# Cell_Module_v1.net
KiCad netlist of a schematic drawn in EAGLE
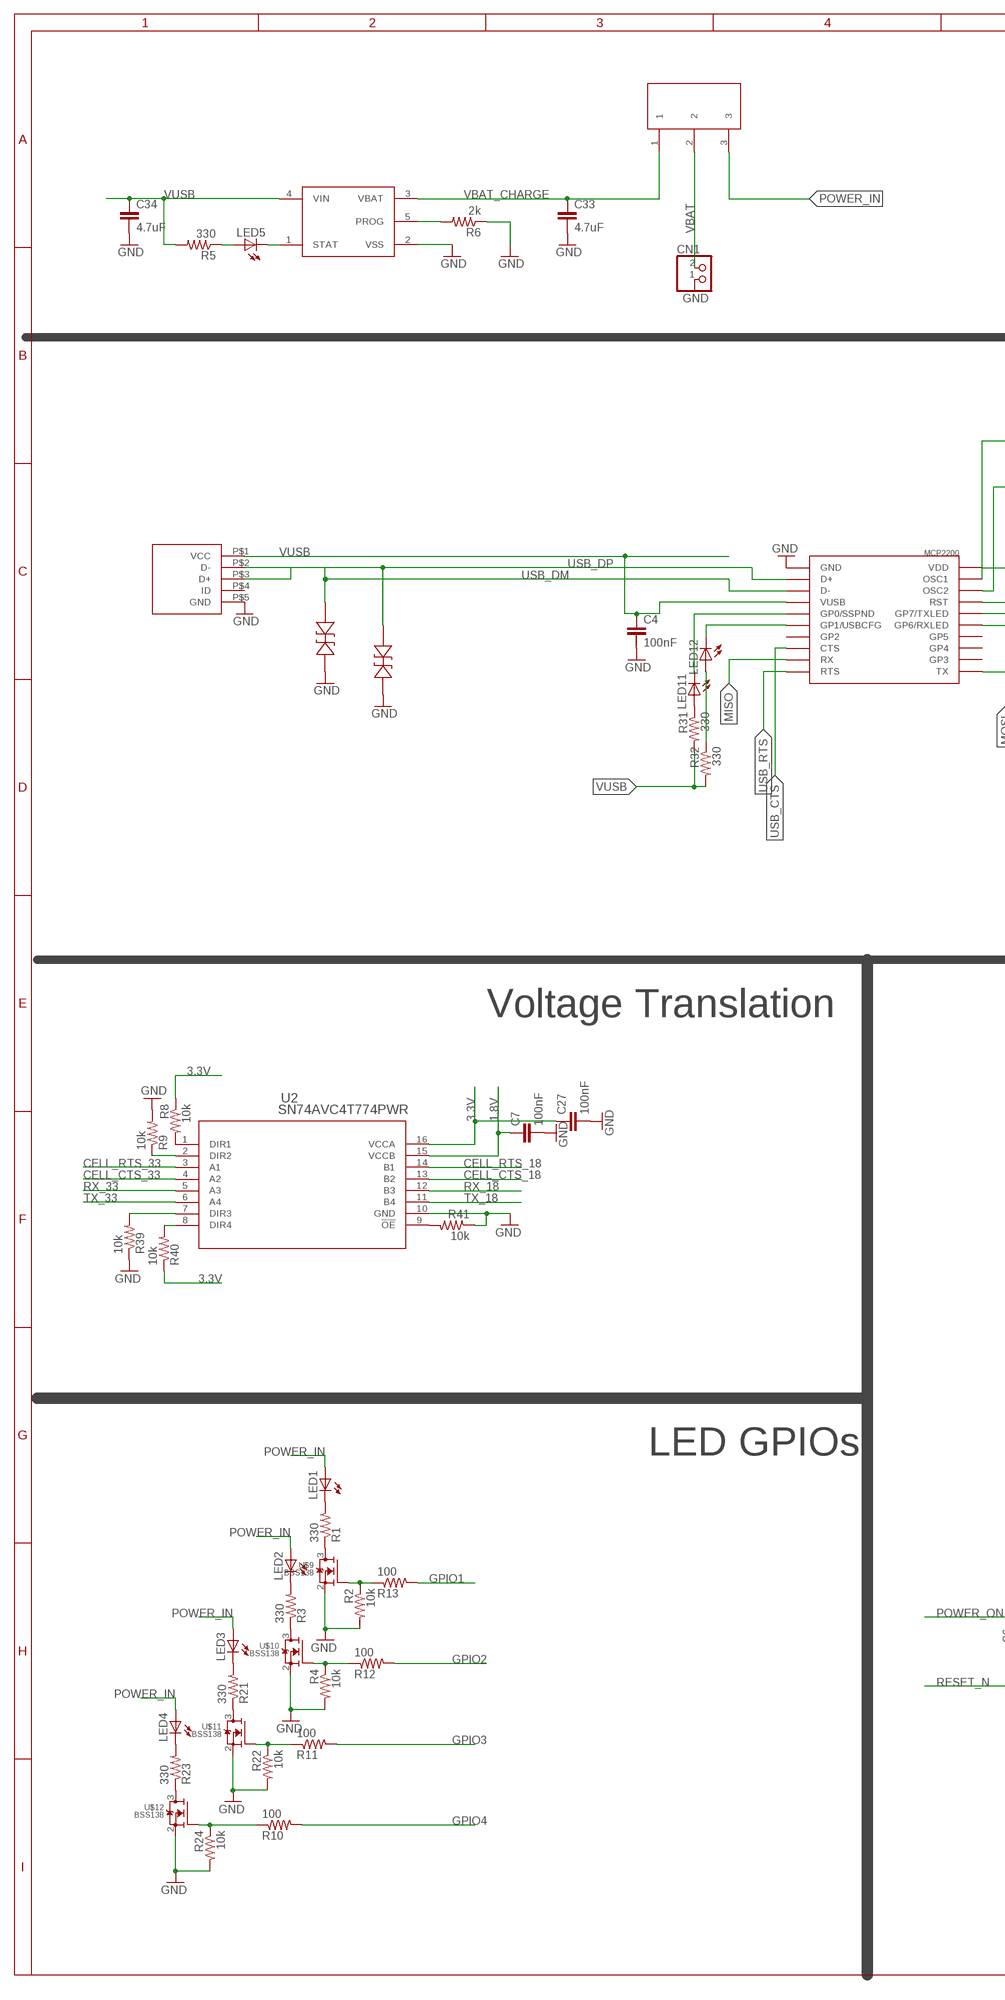
[diagram p0: schematic, sheet 1, part 1 of 2]
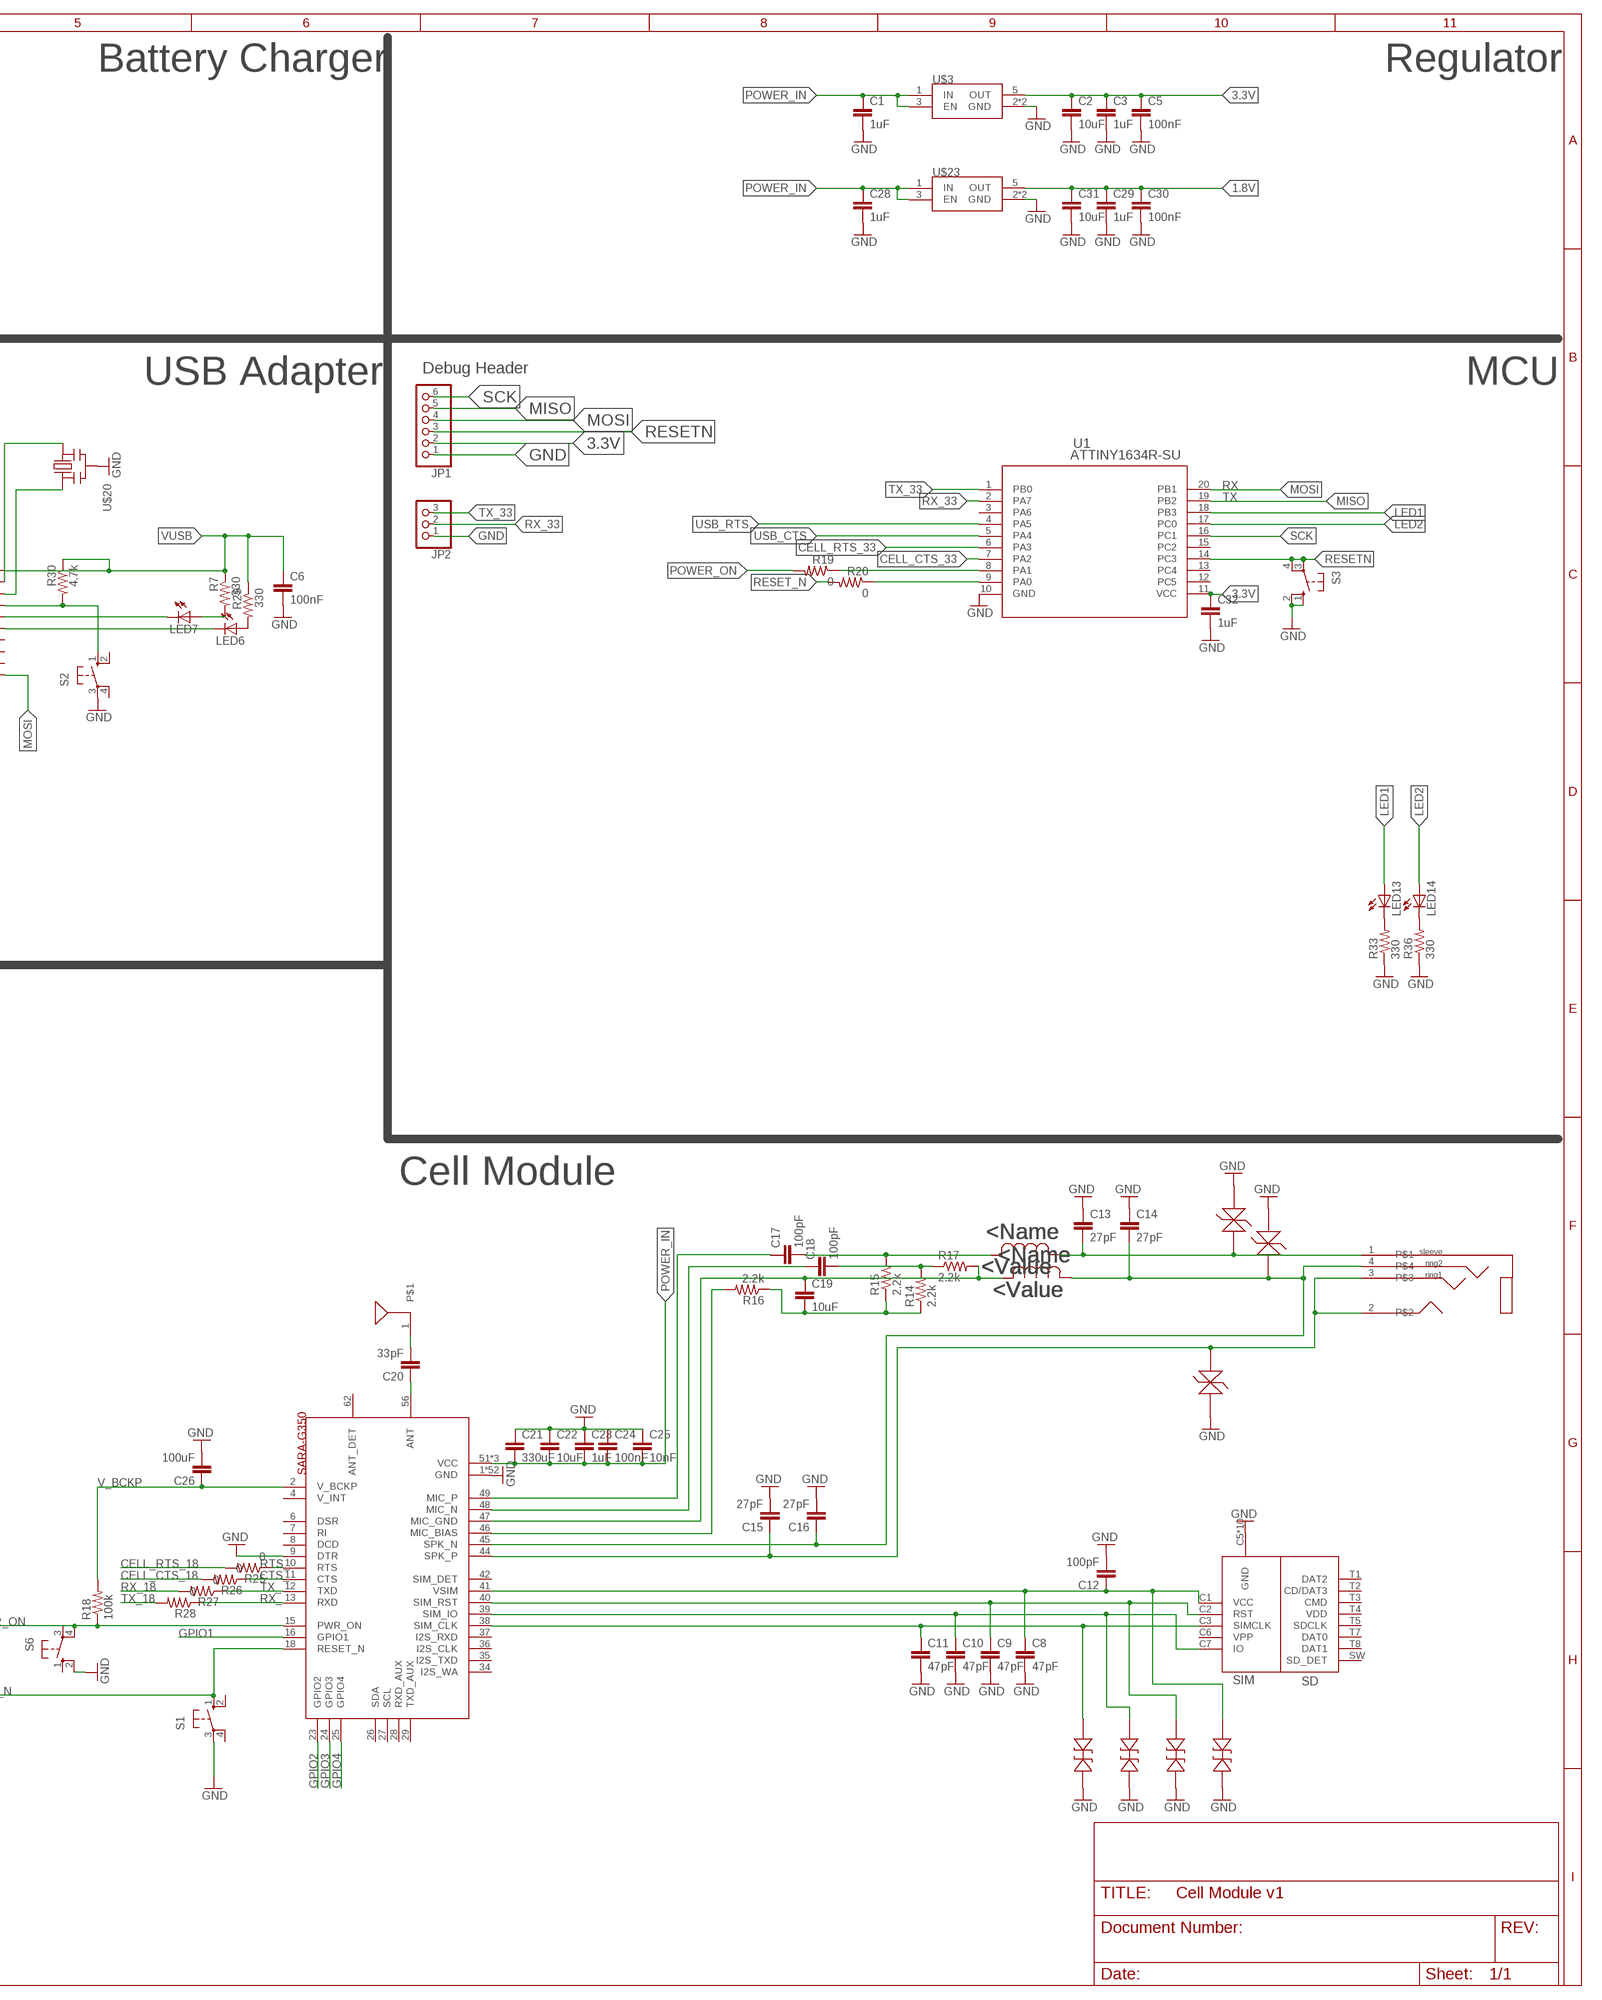
[diagram p1: schematic, sheet 1, part 2 of 2]

(export (version "E")
  (design (tool "Eeschema 10.0.6"))
  (components
    (comp (ref "C1")
      (value "1uF")
      (footprint "eagle-import:C0402")
      (libsource (lib "eagle-import") (part "C-EUC0402"))
    )
    (comp (ref "C2")
      (value "10uF")
      (footprint "eagle-import:C0603")
      (libsource (lib "eagle-import") (part "C-EUC0603"))
    )
    (comp (ref "C3")
      (value "1uF")
      (footprint "eagle-import:C0402")
      (libsource (lib "eagle-import") (part "C-EUC0402"))
    )
    (comp (ref "C4")
      (value "100nF")
      (footprint "eagle-import:C0402")
      (libsource (lib "eagle-import") (part "C-EUC0402"))
    )
    (comp (ref "C5")
      (value "100nF")
      (footprint "eagle-import:C0402")
      (libsource (lib "eagle-import") (part "C-EUC0402"))
    )
    (comp (ref "C6")
      (value "100nF")
      (footprint "eagle-import:C0402")
      (libsource (lib "eagle-import") (part "C-EUC0402"))
    )
    (comp (ref "C7")
      (value "100nF")
      (footprint "eagle-import:C0402")
      (libsource (lib "eagle-import") (part "C-EUC0402"))
    )
    (comp (ref "C8")
      (value "47pF")
      (footprint "eagle-import:C0402")
      (libsource (lib "eagle-import") (part "C-EUC0402"))
    )
    (comp (ref "C9")
      (value "47pF")
      (footprint "eagle-import:C0402")
      (libsource (lib "eagle-import") (part "C-EUC0402"))
    )
    (comp (ref "C10")
      (value "47pF")
      (footprint "eagle-import:C0402")
      (libsource (lib "eagle-import") (part "C-EUC0402"))
    )
    (comp (ref "C11")
      (value "47pF")
      (footprint "eagle-import:C0402")
      (libsource (lib "eagle-import") (part "C-EUC0402"))
    )
    (comp (ref "C12")
      (value "100pF")
      (footprint "eagle-import:C0402")
      (libsource (lib "eagle-import") (part "C-EUC0402"))
    )
    (comp (ref "C13")
      (value "27pF")
      (footprint "eagle-import:C0402")
      (libsource (lib "eagle-import") (part "C-EUC0402"))
    )
    (comp (ref "C14")
      (value "27pF")
      (footprint "eagle-import:C0402")
      (libsource (lib "eagle-import") (part "C-EUC0402"))
    )
    (comp (ref "C15")
      (value "27pF")
      (footprint "eagle-import:C0402")
      (libsource (lib "eagle-import") (part "C-EUC0402"))
    )
    (comp (ref "C16")
      (value "27pF")
      (footprint "eagle-import:C0402")
      (libsource (lib "eagle-import") (part "C-EUC0402"))
    )
    (comp (ref "C17")
      (value "100pF")
      (footprint "eagle-import:C0402")
      (libsource (lib "eagle-import") (part "C-EUC0402"))
    )
    (comp (ref "C18")
      (value "100pF")
      (footprint "eagle-import:C0402")
      (libsource (lib "eagle-import") (part "C-EUC0402"))
    )
    (comp (ref "C19")
      (value "10uF")
      (footprint "eagle-import:C0603")
      (libsource (lib "eagle-import") (part "C-EUC0603"))
    )
    (comp (ref "C20")
      (value "33pF")
      (footprint "eagle-import:C0402")
      (libsource (lib "eagle-import") (part "C-EUC0402"))
    )
    (comp (ref "C21")
      (value "330uF")
      (footprint "eagle-import:C1210")
      (libsource (lib "eagle-import") (part "C-EUC1210"))
    )
    (comp (ref "C22")
      (value "10uF")
      (footprint "eagle-import:C0603")
      (libsource (lib "eagle-import") (part "C-EUC0603"))
    )
    (comp (ref "C23")
      (value "1uF")
      (footprint "eagle-import:C0402")
      (libsource (lib "eagle-import") (part "C-EUC0402"))
    )
    (comp (ref "C24")
      (value "100nF")
      (footprint "eagle-import:C0402")
      (libsource (lib "eagle-import") (part "C-EUC0402"))
    )
    (comp (ref "C25")
      (value "10nF")
      (footprint "eagle-import:C0402")
      (libsource (lib "eagle-import") (part "C-EUC0402"))
    )
    (comp (ref "C26")
      (value "100uF")
      (footprint "eagle-import:C1206")
      (libsource (lib "eagle-import") (part "C-EUC1206"))
    )
    (comp (ref "C27")
      (value "100nF")
      (footprint "eagle-import:C0402")
      (libsource (lib "eagle-import") (part "C-EUC0402"))
    )
    (comp (ref "C28")
      (value "1uF")
      (footprint "eagle-import:C0402")
      (libsource (lib "eagle-import") (part "C-EUC0402"))
    )
    (comp (ref "C29")
      (value "1uF")
      (footprint "eagle-import:C0402")
      (libsource (lib "eagle-import") (part "C-EUC0402"))
    )
    (comp (ref "C30")
      (value "100nF")
      (footprint "eagle-import:C0402")
      (libsource (lib "eagle-import") (part "C-EUC0402"))
    )
    (comp (ref "C31")
      (value "10uF")
      (footprint "eagle-import:C0603")
      (libsource (lib "eagle-import") (part "C-EUC0603"))
    )
    (comp (ref "C32")
      (value "1uF")
      (footprint "eagle-import:C0402")
      (libsource (lib "eagle-import") (part "C-EUC0402"))
    )
    (comp (ref "C33")
      (value "4.7uF")
      (footprint "eagle-import:C0402")
      (libsource (lib "eagle-import") (part "C-EUC0402"))
    )
    (comp (ref "C34")
      (value "4.7uF")
      (footprint "eagle-import:C0402")
      (libsource (lib "eagle-import") (part "C-EUC0402"))
    )
    (comp (ref "CN1")
      (value "JST_2PIN-THM")
      (footprint "eagle-import:JST-PH-2-THM")
      (libsource (lib "eagle-import") (part "JST_2PIN-THM"))
    )
    (comp (ref "CR1")
      (value "PESD0402-140")
      (footprint "eagle-import:PESD0402")
      (fields (field (name "MANUFACTURER_PART_NUMBER") "PESD0402140"))
      (libsource (lib "eagle-import") (part "PESD0402-140"))
    )
    (comp (ref "CR2")
      (value "PESD0402-140")
      (footprint "eagle-import:PESD0402")
      (fields (field (name "MANUFACTURER_PART_NUMBER") "PESD0402140"))
      (libsource (lib "eagle-import") (part "PESD0402-140"))
    )
    (comp (ref "CR3")
      (value "PESD0402-140")
      (footprint "eagle-import:PESD0402")
      (fields (field (name "MANUFACTURER_PART_NUMBER") "PESD0402140"))
      (libsource (lib "eagle-import") (part "PESD0402-140"))
    )
    (comp (ref "CR4")
      (value "PESD0402-140")
      (footprint "eagle-import:PESD0402")
      (fields (field (name "MANUFACTURER_PART_NUMBER") "PESD0402140"))
      (libsource (lib "eagle-import") (part "PESD0402-140"))
    )
    (comp (ref "CR5")
      (value "PESD0402-140")
      (footprint "eagle-import:PESD0402")
      (fields (field (name "MANUFACTURER_PART_NUMBER") "PESD0402140"))
      (libsource (lib "eagle-import") (part "PESD0402-140"))
    )
    (comp (ref "CR6")
      (value "PESD0402-140")
      (footprint "eagle-import:PESD0402")
      (fields (field (name "MANUFACTURER_PART_NUMBER") "PESD0402140"))
      (libsource (lib "eagle-import") (part "PESD0402-140"))
    )
    (comp (ref "JP1")
      (value "PINHD-1X6")
      (footprint "eagle-import:1X06")
      (libsource (lib "eagle-import") (part "PINHD-1X6"))
    )
    (comp (ref "JP2")
      (value "PINHD-1X3")
      (footprint "eagle-import:1X03")
      (libsource (lib "eagle-import") (part "PINHD-1X3"))
    )
    (comp (ref "LED1")
      (value "LEDCHIP-LED0805")
      (footprint "eagle-import:CHIP-LED0805")
      (libsource (lib "eagle-import") (part "LEDCHIP-LED0805"))
    )
    (comp (ref "LED2")
      (value "LEDCHIP-LED0805")
      (footprint "eagle-import:CHIP-LED0805")
      (libsource (lib "eagle-import") (part "LEDCHIP-LED0805"))
    )
    (comp (ref "LED3")
      (value "LEDCHIP-LED0805")
      (footprint "eagle-import:CHIP-LED0805")
      (libsource (lib "eagle-import") (part "LEDCHIP-LED0805"))
    )
    (comp (ref "LED4")
      (value "LEDCHIP-LED0805")
      (footprint "eagle-import:CHIP-LED0805")
      (libsource (lib "eagle-import") (part "LEDCHIP-LED0805"))
    )
    (comp (ref "LED5")
      (value "LEDCHIP-LED0603")
      (footprint "eagle-import:CHIP-LED0603")
      (libsource (lib "eagle-import") (part "LEDCHIP-LED0603"))
    )
    (comp (ref "LED6")
      (value "LEDCHIP-LED0805")
      (footprint "eagle-import:CHIP-LED0805")
      (libsource (lib "eagle-import") (part "LEDCHIP-LED0805"))
    )
    (comp (ref "LED7")
      (value "LEDCHIP-LED0805")
      (footprint "eagle-import:CHIP-LED0805")
      (libsource (lib "eagle-import") (part "LEDCHIP-LED0805"))
    )
    (comp (ref "LED11")
      (value "LEDCHIP-LED0805")
      (footprint "eagle-import:CHIP-LED0805")
      (libsource (lib "eagle-import") (part "LEDCHIP-LED0805"))
    )
    (comp (ref "LED12")
      (value "LEDCHIP-LED0805")
      (footprint "eagle-import:CHIP-LED0805")
      (libsource (lib "eagle-import") (part "LEDCHIP-LED0805"))
    )
    (comp (ref "LED13")
      (value "LEDCHIP-LED0805")
      (footprint "eagle-import:CHIP-LED0805")
      (libsource (lib "eagle-import") (part "LEDCHIP-LED0805"))
    )
    (comp (ref "LED14")
      (value "LEDCHIP-LED0805")
      (footprint "eagle-import:CHIP-LED0805")
      (libsource (lib "eagle-import") (part "LEDCHIP-LED0805"))
    )
    (comp (ref "R1")
      (value "330")
      (footprint "eagle-import:R0402")
      (libsource (lib "eagle-import") (part "R-US_R0402"))
    )
    (comp (ref "R2")
      (value "10k")
      (footprint "eagle-import:R0402")
      (libsource (lib "eagle-import") (part "R-US_R0402"))
    )
    (comp (ref "R3")
      (value "330")
      (footprint "eagle-import:R0402")
      (libsource (lib "eagle-import") (part "R-US_R0402"))
    )
    (comp (ref "R4")
      (value "10k")
      (footprint "eagle-import:R0402")
      (libsource (lib "eagle-import") (part "R-US_R0402"))
    )
    (comp (ref "R5")
      (value "330")
      (footprint "eagle-import:R0402")
      (libsource (lib "eagle-import") (part "R-US_R0402"))
    )
    (comp (ref "R6")
      (value "2k")
      (footprint "eagle-import:R0402")
      (libsource (lib "eagle-import") (part "R-US_R0402"))
    )
    (comp (ref "R7")
      (value "330")
      (footprint "eagle-import:R0402")
      (libsource (lib "eagle-import") (part "R-US_R0402"))
    )
    (comp (ref "R8")
      (value "10k")
      (footprint "eagle-import:R0402")
      (libsource (lib "eagle-import") (part "R-US_R0402"))
    )
    (comp (ref "R9")
      (value "10k")
      (footprint "eagle-import:R0402")
      (libsource (lib "eagle-import") (part "R-US_R0402"))
    )
    (comp (ref "R10")
      (value "100")
      (footprint "eagle-import:R0402")
      (libsource (lib "eagle-import") (part "R-US_R0402"))
    )
    (comp (ref "R11")
      (value "100")
      (footprint "eagle-import:R0402")
      (libsource (lib "eagle-import") (part "R-US_R0402"))
    )
    (comp (ref "R12")
      (value "100")
      (footprint "eagle-import:R0402")
      (libsource (lib "eagle-import") (part "R-US_R0402"))
    )
    (comp (ref "R13")
      (value "100")
      (footprint "eagle-import:R0402")
      (libsource (lib "eagle-import") (part "R-US_R0402"))
    )
    (comp (ref "R14")
      (value "2.2k")
      (footprint "eagle-import:R0402")
      (libsource (lib "eagle-import") (part "R-US_R0402"))
    )
    (comp (ref "R15")
      (value "2.2k")
      (footprint "eagle-import:R0402")
      (libsource (lib "eagle-import") (part "R-US_R0402"))
    )
    (comp (ref "R16")
      (value "2.2k")
      (footprint "eagle-import:R0402")
      (libsource (lib "eagle-import") (part "R-US_R0402"))
    )
    (comp (ref "R17")
      (value "2.2k")
      (footprint "eagle-import:R0402")
      (libsource (lib "eagle-import") (part "R-US_R0402"))
    )
    (comp (ref "R18")
      (value "100k")
      (footprint "eagle-import:R0402")
      (libsource (lib "eagle-import") (part "R-US_R0402"))
    )
    (comp (ref "R19")
      (value "0")
      (footprint "eagle-import:R0402")
      (libsource (lib "eagle-import") (part "R-US_R0402"))
    )
    (comp (ref "R20")
      (value "0")
      (footprint "eagle-import:R0402")
      (libsource (lib "eagle-import") (part "R-US_R0402"))
    )
    (comp (ref "R21")
      (value "330")
      (footprint "eagle-import:R0402")
      (libsource (lib "eagle-import") (part "R-US_R0402"))
    )
    (comp (ref "R22")
      (value "10k")
      (footprint "eagle-import:R0402")
      (libsource (lib "eagle-import") (part "R-US_R0402"))
    )
    (comp (ref "R23")
      (value "330")
      (footprint "eagle-import:R0402")
      (libsource (lib "eagle-import") (part "R-US_R0402"))
    )
    (comp (ref "R24")
      (value "10k")
      (footprint "eagle-import:R0402")
      (libsource (lib "eagle-import") (part "R-US_R0402"))
    )
    (comp (ref "R25")
      (value "0")
      (footprint "eagle-import:R0402")
      (libsource (lib "eagle-import") (part "R-US_R0402"))
    )
    (comp (ref "R26")
      (value "0")
      (footprint "eagle-import:R0402")
      (libsource (lib "eagle-import") (part "R-US_R0402"))
    )
    (comp (ref "R27")
      (value "0")
      (footprint "eagle-import:R0402")
      (libsource (lib "eagle-import") (part "R-US_R0402"))
    )
    (comp (ref "R28")
      (value "0")
      (footprint "eagle-import:R0402")
      (libsource (lib "eagle-import") (part "R-US_R0402"))
    )
    (comp (ref "R29")
      (value "330")
      (footprint "eagle-import:R0402")
      (libsource (lib "eagle-import") (part "R-US_R0402"))
    )
    (comp (ref "R30")
      (value "4.7k")
      (footprint "eagle-import:R0402")
      (libsource (lib "eagle-import") (part "R-US_R0402"))
    )
    (comp (ref "R31")
      (value "330")
      (footprint "eagle-import:R0402")
      (libsource (lib "eagle-import") (part "R-US_R0402"))
    )
    (comp (ref "R32")
      (value "330")
      (footprint "eagle-import:R0402")
      (libsource (lib "eagle-import") (part "R-US_R0402"))
    )
    (comp (ref "R33")
      (value "330")
      (footprint "eagle-import:R0402")
      (libsource (lib "eagle-import") (part "R-US_R0402"))
    )
    (comp (ref "R36")
      (value "330")
      (footprint "eagle-import:R0402")
      (libsource (lib "eagle-import") (part "R-US_R0402"))
    )
    (comp (ref "R39")
      (value "10k")
      (footprint "eagle-import:R0402")
      (libsource (lib "eagle-import") (part "R-US_R0402"))
    )
    (comp (ref "R40")
      (value "10k")
      (footprint "eagle-import:R0402")
      (libsource (lib "eagle-import") (part "R-US_R0402"))
    )
    (comp (ref "R41")
      (value "10k")
      (footprint "eagle-import:R0402")
      (libsource (lib "eagle-import") (part "R-US_R0402"))
    )
    (comp (ref "S1")
      (value "10-XX")
      (footprint "eagle-import:B3F-10XX")
      (fields (field (name "MPN") "B3F-1000"))
      (libsource (lib "eagle-import") (part "10-XX"))
    )
    (comp (ref "S2")
      (value "10-XX")
      (footprint "eagle-import:B3F-10XX")
      (fields (field (name "MPN") "B3F-1000"))
      (libsource (lib "eagle-import") (part "10-XX"))
    )
    (comp (ref "S3")
      (value "10-XX")
      (footprint "eagle-import:B3F-10XX")
      (fields (field (name "MPN") "B3F-1000"))
      (libsource (lib "eagle-import") (part "10-XX"))
    )
    (comp (ref "S6")
      (value "10-XX")
      (footprint "eagle-import:B3F-10XX")
      (fields (field (name "MPN") "B3F-1000"))
      (libsource (lib "eagle-import") (part "10-XX"))
    )
    (comp (ref "U$1")
      (value "SARA-G350")
      (footprint "eagle-import:SARA-G350")
      (libsource (lib "eagle-import") (part "SARA-G350"))
    )
    (comp (ref "U$2")
      (value "SIM_SD_MOLEX")
      (footprint "eagle-import:SIM_SD_MOLEX")
      (libsource (lib "eagle-import") (part "SIM_SD_MOLEX"))
    )
    (comp (ref "U$3")
      (value "TPS782XX")
      (footprint "eagle-import:SOT23-5L")
      (libsource (lib "eagle-import") (part "TPS782XX"))
    )
    (comp (ref "U$4")
      (value "MCP73831")
      (footprint "eagle-import:SOT23-5L")
      (libsource (lib "eagle-import") (part "MCP73831"))
    )
    (comp (ref "U$5")
      (value "MICRO_USB")
      (footprint "eagle-import:MOLEX_USB")
      (libsource (lib "eagle-import") (part "MICRO_USB"))
    )
    (comp (ref "U$6")
      (value "SPDT_THRU")
      (footprint "eagle-import:SPDT_THRU")
      (libsource (lib "eagle-import") (part "SPDT_THRU"))
    )
    (comp (ref "U$7")
      (value "A10340")
      (footprint "eagle-import:A10340")
      (libsource (lib "eagle-import") (part "A10340"))
    )
    (comp (ref "U$8")
      (value "SJ-43514-SMT-TR")
      (footprint "eagle-import:SJ-43514-SMT-TR")
      (libsource (lib "eagle-import") (part "SJ-43514-SMT-TR"))
    )
    (comp (ref "U$9")
      (value "BSS138")
      (footprint "eagle-import:SOT23-3")
      (libsource (lib "eagle-import") (part "BSS138"))
    )
    (comp (ref "U$10")
      (value "BSS138")
      (footprint "eagle-import:SOT23-3")
      (libsource (lib "eagle-import") (part "BSS138"))
    )
    (comp (ref "U$11")
      (value "BSS138")
      (footprint "eagle-import:SOT23-3")
      (libsource (lib "eagle-import") (part "BSS138"))
    )
    (comp (ref "U$12")
      (value "BSS138")
      (footprint "eagle-import:SOT23-3")
      (libsource (lib "eagle-import") (part "BSS138"))
    )
    (comp (ref "U$13")
      (value "LQG15HS82NJ02")
      (footprint "eagle-import:0402")
      (libsource (lib "eagle-import") (part "LQG15HS82NJ02"))
    )
    (comp (ref "U$14")
      (value "LQG15HS82NJ02")
      (footprint "eagle-import:0402")
      (libsource (lib "eagle-import") (part "LQG15HS82NJ02"))
    )
    (comp (ref "U$16")
      (value "CG0402MLE-18G")
      (footprint "eagle-import:0402")
      (libsource (lib "eagle-import") (part "CG0402MLE-18G"))
    )
    (comp (ref "U$17")
      (value "CG0402MLE-18G")
      (footprint "eagle-import:0402")
      (libsource (lib "eagle-import") (part "CG0402MLE-18G"))
    )
    (comp (ref "U$18")
      (value "CG0402MLE-18G")
      (footprint "eagle-import:0402")
      (libsource (lib "eagle-import") (part "CG0402MLE-18G"))
    )
    (comp (ref "U$19")
      (value "MCP2200")
      (footprint "eagle-import:SOIC20_65PITCH_LARGER")
      (libsource (lib "eagle-import") (part "MCP2200"))
    )
    (comp (ref "U$20")
      (value "CERMOSCILL-AWCSR")
      (footprint "eagle-import:AWCSR")
      (libsource (lib "eagle-import") (part "CERMOSCILL-AWCSR"))
    )
    (comp (ref "U$23")
      (value "TPS782XX")
      (footprint "eagle-import:SOT23-5L")
      (libsource (lib "eagle-import") (part "TPS782XX"))
    )
    (comp (ref "U1")
      (value "ATTINY1634R-SU")
      (footprint "eagle-import:20S2")
      (fields (field (name "MANUFACTURER_PART_NUMBER") "attiny1634rsu"))
      (libsource (lib "eagle-import") (part "ATTINY1634R-SU"))
    )
    (comp (ref "U2")
      (value "SN74AVC4T774PWR")
      (footprint "eagle-import:PW16")
      (libsource (lib "eagle-import") (part "SN74AVC4T774PWR"))
    )
  )
  (nets
    (net (code "1") (name "/CELL_CTS_18") (class "Default")
      (node (ref "R26") (pin "2") (pinfunction "2_2") (pintype "passive"))
      (node (ref "U2") (pin "13") (pinfunction "B2_13") (pintype "bidirectional"))
    )
    (net (code "2") (name "/CELL_RTS_18") (class "Default")
      (node (ref "R25") (pin "2") (pinfunction "2_2") (pintype "passive"))
      (node (ref "U2") (pin "14") (pinfunction "B1_14") (pintype "bidirectional"))
    )
    (net (code "3") (name "/CTS_") (class "Default")
      (node (ref "R26") (pin "1") (pinfunction "1_1") (pintype "passive"))
      (node (ref "U$1") (pin "11") (pinfunction "CTS_11") (pintype "bidirectional"))
    )
    (net (code "4") (name "/GPIO1") (class "Default")
      (node (ref "R13") (pin "2") (pinfunction "2_2") (pintype "passive"))
      (node (ref "U$1") (pin "16") (pinfunction "GPIO1_16") (pintype "bidirectional"))
    )
    (net (code "5") (name "/GPIO2") (class "Default")
      (node (ref "R12") (pin "2") (pinfunction "2_2") (pintype "passive"))
      (node (ref "U$1") (pin "23") (pinfunction "GPIO2_23") (pintype "bidirectional"))
    )
    (net (code "6") (name "/GPIO3") (class "Default")
      (node (ref "R11") (pin "2") (pinfunction "2_2") (pintype "passive"))
      (node (ref "U$1") (pin "24") (pinfunction "GPIO3_24") (pintype "bidirectional"))
    )
    (net (code "7") (name "/GPIO4") (class "Default")
      (node (ref "R10") (pin "2") (pinfunction "2_2") (pintype "passive"))
      (node (ref "U$1") (pin "25") (pinfunction "GPIO4_25") (pintype "bidirectional"))
    )
    (net (code "8") (name "/RTS_") (class "Default")
      (node (ref "R25") (pin "1") (pinfunction "1_1") (pintype "passive"))
      (node (ref "U$1") (pin "10") (pinfunction "RTS_10") (pintype "bidirectional"))
    )
    (net (code "9") (name "/RX_") (class "Default")
      (node (ref "R28") (pin "1") (pinfunction "1_1") (pintype "passive"))
      (node (ref "U$1") (pin "13") (pinfunction "RXD_13") (pintype "bidirectional"))
    )
    (net (code "10") (name "/RX_18") (class "Default")
      (node (ref "R27") (pin "2") (pinfunction "2_2") (pintype "passive"))
      (node (ref "U2") (pin "12") (pinfunction "B3_12") (pintype "bidirectional"))
    )
    (net (code "11") (name "/TX_") (class "Default")
      (node (ref "R27") (pin "1") (pinfunction "1_1") (pintype "passive"))
      (node (ref "U$1") (pin "12") (pinfunction "TXD_12") (pintype "bidirectional"))
    )
    (net (code "12") (name "/TX_18") (class "Default")
      (node (ref "R28") (pin "2") (pinfunction "2_2") (pintype "passive"))
      (node (ref "U2") (pin "11") (pinfunction "B4_11") (pintype "bidirectional"))
    )
    (net (code "13") (name "/USB_DM") (class "Default")
      (node (ref "CR5") (pin "2") (pinfunction "22_2") (pintype "passive"))
      (node (ref "U$19") (pin "18") (pinfunction "D-_18") (pintype "bidirectional"))
      (node (ref "U$5") (pin "P$2") (pinfunction "D-_P$2") (pintype "bidirectional"))
    )
    (net (code "14") (name "/USB_DP") (class "Default")
      (node (ref "CR6") (pin "2") (pinfunction "22_2") (pintype "passive"))
      (node (ref "U$19") (pin "19") (pinfunction "D+_19") (pintype "bidirectional"))
      (node (ref "U$5") (pin "P$3") (pinfunction "D+_P$3") (pintype "bidirectional"))
    )
    (net (code "15") (name "/VBAT") (class "Default")
      (node (ref "CN1") (pin "2") (pinfunction "1_2") (pintype "passive"))
      (node (ref "U$6") (pin "2") (pinfunction "2_2") (pintype "bidirectional"))
    )
    (net (code "16") (name "/VBAT_CHARGE") (class "Default")
      (node (ref "C33") (pin "1") (pinfunction "1_1") (pintype "passive"))
      (node (ref "U$4") (pin "3") (pinfunction "VBAT_3") (pintype "bidirectional"))
      (node (ref "U$6") (pin "1") (pinfunction "1_1") (pintype "bidirectional"))
    )
    (net (code "17") (name "/V_BCKP") (class "Default")
      (node (ref "C26") (pin "1") (pinfunction "1_1") (pintype "passive"))
      (node (ref "R18") (pin "2") (pinfunction "2_2") (pintype "passive"))
      (node (ref "U$1") (pin "2") (pinfunction "V_BCKP_2") (pintype "bidirectional"))
    )
    (net (code "18") (name "1.8V") (class "Default")
      (node (ref "C29") (pin "1") (pinfunction "1_1") (pintype "passive"))
      (node (ref "C30") (pin "1") (pinfunction "1_1") (pintype "passive"))
      (node (ref "C31") (pin "1") (pinfunction "1_1") (pintype "passive"))
      (node (ref "C7") (pin "1") (pinfunction "1_1") (pintype "passive"))
      (node (ref "U$23") (pin "5") (pinfunction "OUT_5") (pintype "bidirectional"))
      (node (ref "U2") (pin "15") (pinfunction "VCCB_15") (pintype "power_in"))
    )
    (net (code "19") (name "3.3V") (class "Default")
      (node (ref "C2") (pin "1") (pinfunction "1_1") (pintype "passive"))
      (node (ref "C27") (pin "1") (pinfunction "1_1") (pintype "passive"))
      (node (ref "C3") (pin "1") (pinfunction "1_1") (pintype "passive"))
      (node (ref "C32") (pin "1") (pinfunction "1_1") (pintype "passive"))
      (node (ref "C5") (pin "1") (pinfunction "1_1") (pintype "passive"))
      (node (ref "JP1") (pin "2") (pinfunction "2_2") (pintype "passive"))
      (node (ref "R40") (pin "1") (pinfunction "1_1") (pintype "passive"))
      (node (ref "R8") (pin "1") (pinfunction "1_1") (pintype "passive"))
      (node (ref "U$3") (pin "5") (pinfunction "OUT_5") (pintype "bidirectional"))
      (node (ref "U1") (pin "11") (pinfunction "VCC_11") (pintype "power_in"))
      (node (ref "U2") (pin "16") (pinfunction "VCCA_16") (pintype "power_in"))
    )
    (net (code "20") (name "CELL_CTS_33") (class "Default")
      (node (ref "U1") (pin "7") (pinfunction "PA2_7") (pintype "bidirectional"))
      (node (ref "U2") (pin "4") (pinfunction "A2_4") (pintype "bidirectional"))
    )
    (net (code "21") (name "CELL_RTS_33") (class "Default")
      (node (ref "U1") (pin "6") (pinfunction "PA3_6") (pintype "bidirectional"))
      (node (ref "U2") (pin "3") (pinfunction "A1_3") (pintype "bidirectional"))
    )
    (net (code "22") (name "GND") (class "Default")
      (node (ref "C1") (pin "2") (pinfunction "2_2") (pintype "passive"))
      (node (ref "C10") (pin "2") (pinfunction "2_2") (pintype "passive"))
      (node (ref "C11") (pin "2") (pinfunction "2_2") (pintype "passive"))
      (node (ref "C12") (pin "2") (pinfunction "2_2") (pintype "passive"))
      (node (ref "C13") (pin "1") (pinfunction "1_1") (pintype "passive"))
      (node (ref "C14") (pin "1") (pinfunction "1_1") (pintype "passive"))
      (node (ref "C15") (pin "2") (pinfunction "2_2") (pintype "passive"))
      (node (ref "C16") (pin "2") (pinfunction "2_2") (pintype "passive"))
      (node (ref "C2") (pin "2") (pinfunction "2_2") (pintype "passive"))
      (node (ref "C21") (pin "1") (pinfunction "1_1") (pintype "passive"))
      (node (ref "C22") (pin "1") (pinfunction "1_1") (pintype "passive"))
      (node (ref "C23") (pin "1") (pinfunction "1_1") (pintype "passive"))
      (node (ref "C24") (pin "1") (pinfunction "1_1") (pintype "passive"))
      (node (ref "C25") (pin "1") (pinfunction "1_1") (pintype "passive"))
      (node (ref "C26") (pin "2") (pinfunction "2_2") (pintype "passive"))
      (node (ref "C27") (pin "2") (pinfunction "2_2") (pintype "passive"))
      (node (ref "C28") (pin "2") (pinfunction "2_2") (pintype "passive"))
      (node (ref "C29") (pin "2") (pinfunction "2_2") (pintype "passive"))
      (node (ref "C3") (pin "2") (pinfunction "2_2") (pintype "passive"))
      (node (ref "C30") (pin "2") (pinfunction "2_2") (pintype "passive"))
      (node (ref "C31") (pin "2") (pinfunction "2_2") (pintype "passive"))
      (node (ref "C32") (pin "2") (pinfunction "2_2") (pintype "passive"))
      (node (ref "C33") (pin "2") (pinfunction "2_2") (pintype "passive"))
      (node (ref "C34") (pin "2") (pinfunction "2_2") (pintype "passive"))
      (node (ref "C4") (pin "2") (pinfunction "2_2") (pintype "passive"))
      (node (ref "C5") (pin "2") (pinfunction "2_2") (pintype "passive"))
      (node (ref "C6") (pin "2") (pinfunction "2_2") (pintype "passive"))
      (node (ref "C7") (pin "2") (pinfunction "2_2") (pintype "passive"))
      (node (ref "C8") (pin "2") (pinfunction "2_2") (pintype "passive"))
      (node (ref "C9") (pin "2") (pinfunction "2_2") (pintype "passive"))
      (node (ref "CN1") (pin "1") (pinfunction "2_1") (pintype "passive"))
      (node (ref "CR1") (pin "1") (pinfunction "11_1") (pintype "passive"))
      (node (ref "CR2") (pin "1") (pinfunction "11_1") (pintype "passive"))
      (node (ref "CR3") (pin "1") (pinfunction "11_1") (pintype "passive"))
      (node (ref "CR4") (pin "1") (pinfunction "11_1") (pintype "passive"))
      (node (ref "CR5") (pin "1") (pinfunction "11_1") (pintype "passive"))
      (node (ref "CR6") (pin "1") (pinfunction "11_1") (pintype "passive"))
      (node (ref "JP1") (pin "1") (pinfunction "1_1") (pintype "passive"))
      (node (ref "JP2") (pin "1") (pinfunction "1_1") (pintype "passive"))
      (node (ref "R2") (pin "2") (pinfunction "2_2") (pintype "passive"))
      (node (ref "R22") (pin "2") (pinfunction "2_2") (pintype "passive"))
      (node (ref "R24") (pin "2") (pinfunction "2_2") (pintype "passive"))
      (node (ref "R33") (pin "1") (pinfunction "1_1") (pintype "passive"))
      (node (ref "R36") (pin "1") (pinfunction "1_1") (pintype "passive"))
      (node (ref "R39") (pin "1") (pinfunction "1_1") (pintype "passive"))
      (node (ref "R4") (pin "2") (pinfunction "2_2") (pintype "passive"))
      (node (ref "R41") (pin "1") (pinfunction "1_1") (pintype "passive"))
      (node (ref "R6") (pin "1") (pinfunction "1_1") (pintype "passive"))
      (node (ref "R9") (pin "2") (pinfunction "2_2") (pintype "passive"))
      (node (ref "S1") (pin "3") (pinfunction "P_3") (pintype "passive"))
      (node (ref "S2") (pin "3") (pinfunction "P_3") (pintype "passive"))
      (node (ref "S3") (pin "1") (pinfunction "S_1") (pintype "passive"))
      (node (ref "S3") (pin "2") (pinfunction "S1_2") (pintype "passive"))
      (node (ref "S6") (pin "2") (pinfunction "S1_2") (pintype "passive"))
      (node (ref "U$1") (pin "1") (pinfunction "GND_1") (pintype "bidirectional"))
      (node (ref "U$1") (pin "14") (pinfunction "GND_14") (pintype "bidirectional"))
      (node (ref "U$1") (pin "20") (pinfunction "GND_20") (pintype "bidirectional"))
      (node (ref "U$1") (pin "21") (pinfunction "GND_21") (pintype "bidirectional"))
      (node (ref "U$1") (pin "22") (pinfunction "GND_22") (pintype "bidirectional"))
      (node (ref "U$1") (pin "3") (pinfunction "GND_3") (pintype "bidirectional"))
      (node (ref "U$1") (pin "30") (pinfunction "GND_30") (pintype "bidirectional"))
      (node (ref "U$1") (pin "32") (pinfunction "GND_32") (pintype "bidirectional"))
      (node (ref "U$1") (pin "43") (pinfunction "GND_43") (pintype "bidirectional"))
      (node (ref "U$1") (pin "5") (pinfunction "GND_5") (pintype "bidirectional"))
      (node (ref "U$1") (pin "50") (pinfunction "GND_50") (pintype "bidirectional"))
      (node (ref "U$1") (pin "54") (pinfunction "GND_54") (pintype "bidirectional"))
      (node (ref "U$1") (pin "55") (pinfunction "GND_55") (pintype "bidirectional"))
      (node (ref "U$1") (pin "57") (pinfunction "GND_57") (pintype "bidirectional"))
      (node (ref "U$1") (pin "58") (pinfunction "GND_58") (pintype "bidirectional"))
      (node (ref "U$1") (pin "59") (pinfunction "GND_59") (pintype "bidirectional"))
      (node (ref "U$1") (pin "60") (pinfunction "GND_60") (pintype "bidirectional"))
      (node (ref "U$1") (pin "61") (pinfunction "GND_61") (pintype "bidirectional"))
      (node (ref "U$1") (pin "63") (pinfunction "GND_63") (pintype "bidirectional"))
      (node (ref "U$1") (pin "64") (pinfunction "GND_64") (pintype "bidirectional"))
      (node (ref "U$1") (pin "65") (pinfunction "GND_65") (pintype "bidirectional"))
      (node (ref "U$1") (pin "66") (pinfunction "GND_66") (pintype "bidirectional"))
      (node (ref "U$1") (pin "67") (pinfunction "GND_67") (pintype "bidirectional"))
      (node (ref "U$1") (pin "68") (pinfunction "GND_68") (pintype "bidirectional"))
      (node (ref "U$1") (pin "69") (pinfunction "GND_69") (pintype "bidirectional"))
      (node (ref "U$1") (pin "70") (pinfunction "GND_70") (pintype "bidirectional"))
      (node (ref "U$1") (pin "71") (pinfunction "GND_71") (pintype "bidirectional"))
      (node (ref "U$1") (pin "72") (pinfunction "GND_72") (pintype "bidirectional"))
      (node (ref "U$1") (pin "73") (pinfunction "GND_73") (pintype "bidirectional"))
      (node (ref "U$1") (pin "74") (pinfunction "GND_74") (pintype "bidirectional"))
      (node (ref "U$1") (pin "75") (pinfunction "GND_75") (pintype "bidirectional"))
      (node (ref "U$1") (pin "76") (pinfunction "GND_76") (pintype "bidirectional"))
      (node (ref "U$1") (pin "77") (pinfunction "GND_77") (pintype "bidirectional"))
      (node (ref "U$1") (pin "78") (pinfunction "GND_78") (pintype "bidirectional"))
      (node (ref "U$1") (pin "79") (pinfunction "GND_79") (pintype "bidirectional"))
      (node (ref "U$1") (pin "80") (pinfunction "GND_80") (pintype "bidirectional"))
      (node (ref "U$1") (pin "81") (pinfunction "GND_81") (pintype "bidirectional"))
      (node (ref "U$1") (pin "82") (pinfunction "GND_82") (pintype "bidirectional"))
      (node (ref "U$1") (pin "83") (pinfunction "GND_83") (pintype "bidirectional"))
      (node (ref "U$1") (pin "84") (pinfunction "GND_84") (pintype "bidirectional"))
      (node (ref "U$1") (pin "85") (pinfunction "GND_85") (pintype "bidirectional"))
      (node (ref "U$1") (pin "86") (pinfunction "GND_86") (pintype "bidirectional"))
      (node (ref "U$1") (pin "87") (pinfunction "GND_87") (pintype "bidirectional"))
      (node (ref "U$1") (pin "88") (pinfunction "GND_88") (pintype "bidirectional"))
      (node (ref "U$1") (pin "89") (pinfunction "GND_89") (pintype "bidirectional"))
      (node (ref "U$1") (pin "9") (pinfunction "DTR_9") (pintype "bidirectional"))
      (node (ref "U$1") (pin "90") (pinfunction "GND_90") (pintype "bidirectional"))
      (node (ref "U$1") (pin "91") (pinfunction "GND_91") (pintype "bidirectional"))
      (node (ref "U$1") (pin "92") (pinfunction "GND_92") (pintype "bidirectional"))
      (node (ref "U$1") (pin "93") (pinfunction "GND_93") (pintype "bidirectional"))
      (node (ref "U$1") (pin "94") (pinfunction "GND_94") (pintype "bidirectional"))
      (node (ref "U$1") (pin "95") (pinfunction "GND_95") (pintype "bidirectional"))
      (node (ref "U$1") (pin "96") (pinfunction "GND_96") (pintype "bidirectional"))
      (node (ref "U$10") (pin "2") (pinfunction "S_2") (pintype "bidirectional"))
      (node (ref "U$11") (pin "2") (pinfunction "S_2") (pintype "bidirectional"))
      (node (ref "U$12") (pin "2") (pinfunction "S_2") (pintype "bidirectional"))
      (node (ref "U$16") (pin "2") (pinfunction "P$2_2") (pintype "bidirectional"))
      (node (ref "U$17") (pin "1") (pinfunction "P$1_1") (pintype "bidirectional"))
      (node (ref "U$18") (pin "1") (pinfunction "P$1_1") (pintype "bidirectional"))
      (node (ref "U$19") (pin "20") (pinfunction "GND_20") (pintype "bidirectional"))
      (node (ref "U$2") (pin "C5") (pinfunction "GND_C5") (pintype "bidirectional"))
      (node (ref "U$2") (pin "G1") (pinfunction "GND_G1") (pintype "bidirectional"))
      (node (ref "U$2") (pin "G2") (pinfunction "GND_G2") (pintype "bidirectional"))
      (node (ref "U$2") (pin "G3") (pinfunction "GND_G3") (pintype "bidirectional"))
      (node (ref "U$2") (pin "G4") (pinfunction "GND_G4") (pintype "bidirectional"))
      (node (ref "U$2") (pin "G5") (pinfunction "GND_G5") (pintype "bidirectional"))
      (node (ref "U$2") (pin "G6") (pinfunction "GND_G6") (pintype "bidirectional"))
      (node (ref "U$2") (pin "G7") (pinfunction "GND_G7") (pintype "bidirectional"))
      (node (ref "U$2") (pin "G8") (pinfunction "GND_G8") (pintype "bidirectional"))
      (node (ref "U$2") (pin "T6") (pinfunction "GND_T6") (pintype "bidirectional"))
      (node (ref "U$20") (pin "2") (pinfunction "GND_2") (pintype "bidirectional"))
      (node (ref "U$23") (pin "2") (pinfunction "GND_2") (pintype "bidirectional"))
      (node (ref "U$23") (pin "4") (pinfunction "GND_4") (pintype "bidirectional"))
      (node (ref "U$3") (pin "2") (pinfunction "GND_2") (pintype "bidirectional"))
      (node (ref "U$3") (pin "4") (pinfunction "GND_4") (pintype "bidirectional"))
      (node (ref "U$4") (pin "2") (pinfunction "VSS_2") (pintype "bidirectional"))
      (node (ref "U$5") (pin "P$5") (pinfunction "GND_P$5") (pintype "bidirectional"))
      (node (ref "U$9") (pin "2") (pinfunction "S_2") (pintype "bidirectional"))
      (node (ref "U1") (pin "10") (pinfunction "GND_10") (pintype "power_in"))
      (node (ref "U2") (pin "10") (pinfunction "GND_10") (pintype "power_in"))
    )
    (net (code "23") (name "LED1") (class "Default")
      (node (ref "LED13") (pin "A") (pinfunction "A_A") (pintype "passive"))
      (node (ref "U1") (pin "18") (pinfunction "PB3_18") (pintype "bidirectional"))
    )
    (net (code "24") (name "LED2") (class "Default")
      (node (ref "LED14") (pin "A") (pinfunction "A_A") (pintype "passive"))
      (node (ref "U1") (pin "17") (pinfunction "PC0_17") (pintype "bidirectional"))
    )
    (net (code "25") (name "MISO") (class "Default")
      (node (ref "JP1") (pin "5") (pinfunction "5_5") (pintype "passive"))
      (node (ref "U$19") (pin "12") (pinfunction "RX_12") (pintype "bidirectional"))
      (node (ref "U1") (pin "19") (pinfunction "PB2_19") (pintype "bidirectional"))
    )
    (net (code "26") (name "MOSI") (class "Default")
      (node (ref "JP1") (pin "4") (pinfunction "4_4") (pintype "passive"))
      (node (ref "U$19") (pin "10") (pinfunction "TX_10") (pintype "bidirectional"))
      (node (ref "U1") (pin "20") (pinfunction "PB1_20") (pintype "bidirectional"))
    )
    (net (code "27") (name "Net-(C17-Pad2)") (class "Default")
      (node (ref "C17") (pin "2") (pinfunction "2_2") (pintype "passive"))
      (node (ref "R15") (pin "2") (pinfunction "2_2") (pintype "passive"))
      (node (ref "U$13") (pin "2") (pinfunction "2_2") (pintype "passive"))
    )
    (net (code "28") (name "Net-(C18-Pad2)") (class "Default")
      (node (ref "C18") (pin "2") (pinfunction "2_2") (pintype "passive"))
      (node (ref "R14") (pin "2") (pinfunction "2_2") (pintype "passive"))
      (node (ref "R17") (pin "1") (pinfunction "1_1") (pintype "passive"))
    )
    (net (code "29") (name "Net-(C19-Pad2)") (class "Default")
      (node (ref "C19") (pin "2") (pinfunction "2_2") (pintype "passive"))
      (node (ref "R14") (pin "1") (pinfunction "1_1") (pintype "passive"))
      (node (ref "R15") (pin "1") (pinfunction "1_1") (pintype "passive"))
      (node (ref "R16") (pin "1") (pinfunction "1_1") (pintype "passive"))
    )
    (net (code "30") (name "Net-(CR1-22)") (class "Default")
      (node (ref "C11") (pin "1") (pinfunction "1_1") (pintype "passive"))
      (node (ref "CR1") (pin "2") (pinfunction "22_2") (pintype "passive"))
      (node (ref "U$1") (pin "38") (pinfunction "SIM_CLK_38") (pintype "bidirectional"))
      (node (ref "U$2") (pin "C3") (pinfunction "SIMCLK_C3") (pintype "bidirectional"))
    )
    (net (code "31") (name "Net-(CR2-22)") (class "Default")
      (node (ref "C10") (pin "1") (pinfunction "1_1") (pintype "passive"))
      (node (ref "CR2") (pin "2") (pinfunction "22_2") (pintype "passive"))
      (node (ref "U$1") (pin "39") (pinfunction "SIM_IO_39") (pintype "bidirectional"))
      (node (ref "U$2") (pin "C7") (pinfunction "IO_C7") (pintype "bidirectional"))
    )
    (net (code "32") (name "Net-(CR3-22)") (class "Default")
      (node (ref "C9") (pin "1") (pinfunction "1_1") (pintype "passive"))
      (node (ref "CR3") (pin "2") (pinfunction "22_2") (pintype "passive"))
      (node (ref "U$1") (pin "40") (pinfunction "SIM_RST_40") (pintype "bidirectional"))
      (node (ref "U$2") (pin "C2") (pinfunction "RST_C2") (pintype "bidirectional"))
    )
    (net (code "33") (name "Net-(CR4-22)") (class "Default")
      (node (ref "C12") (pin "1") (pinfunction "1_1") (pintype "passive"))
      (node (ref "C8") (pin "1") (pinfunction "1_1") (pintype "passive"))
      (node (ref "CR4") (pin "2") (pinfunction "22_2") (pintype "passive"))
      (node (ref "U$1") (pin "41") (pinfunction "VSIM_41") (pintype "bidirectional"))
      (node (ref "U$2") (pin "C1") (pinfunction "VCC_C1") (pintype "bidirectional"))
    )
    (net (code "34") (name "Net-(LED1-PadC)") (class "Default")
      (node (ref "LED1") (pin "C") (pinfunction "C_C") (pintype "passive"))
      (node (ref "R1") (pin "2") (pinfunction "2_2") (pintype "passive"))
    )
    (net (code "35") (name "Net-(LED2-PadC)") (class "Default")
      (node (ref "LED2") (pin "C") (pinfunction "C_C") (pintype "passive"))
      (node (ref "R3") (pin "2") (pinfunction "2_2") (pintype "passive"))
    )
    (net (code "36") (name "Net-(LED3-PadC)") (class "Default")
      (node (ref "LED3") (pin "C") (pinfunction "C_C") (pintype "passive"))
      (node (ref "R21") (pin "2") (pinfunction "2_2") (pintype "passive"))
    )
    (net (code "37") (name "Net-(LED4-PadC)") (class "Default")
      (node (ref "LED4") (pin "C") (pinfunction "C_C") (pintype "passive"))
      (node (ref "R23") (pin "2") (pinfunction "2_2") (pintype "passive"))
    )
    (net (code "38") (name "Net-(LED5-PadA)") (class "Default")
      (node (ref "LED5") (pin "A") (pinfunction "A_A") (pintype "passive"))
      (node (ref "R5") (pin "1") (pinfunction "1_1") (pintype "passive"))
    )
    (net (code "39") (name "Net-(LED6-PadA)") (class "Default")
      (node (ref "LED6") (pin "A") (pinfunction "A_A") (pintype "passive"))
      (node (ref "R29") (pin "2") (pinfunction "2_2") (pintype "passive"))
    )
    (net (code "40") (name "Net-(LED7-PadA)") (class "Default")
      (node (ref "LED7") (pin "A") (pinfunction "A_A") (pintype "passive"))
      (node (ref "R7") (pin "2") (pinfunction "2_2") (pintype "passive"))
    )
    (net (code "41") (name "Net-(LED11-PadA)") (class "Default")
      (node (ref "LED11") (pin "A") (pinfunction "A_A") (pintype "passive"))
      (node (ref "R31") (pin "1") (pinfunction "1_1") (pintype "passive"))
    )
    (net (code "42") (name "Net-(LED12-PadA)") (class "Default")
      (node (ref "LED12") (pin "A") (pinfunction "A_A") (pintype "passive"))
      (node (ref "R32") (pin "1") (pinfunction "1_1") (pintype "passive"))
    )
    (net (code "43") (name "Net-(LED13-PadC)") (class "Default")
      (node (ref "LED13") (pin "C") (pinfunction "C_C") (pintype "passive"))
      (node (ref "R33") (pin "2") (pinfunction "2_2") (pintype "passive"))
    )
    (net (code "44") (name "Net-(LED14-PadC)") (class "Default")
      (node (ref "LED14") (pin "C") (pinfunction "C_C") (pintype "passive"))
      (node (ref "R36") (pin "2") (pinfunction "2_2") (pintype "passive"))
    )
    (net (code "45") (name "Net-(S2-S)") (class "Default")
      (node (ref "R30") (pin "2") (pinfunction "2_2") (pintype "passive"))
      (node (ref "S2") (pin "1") (pinfunction "S_1") (pintype "passive"))
      (node (ref "U$19") (pin "4") (pinfunction "RST_4") (pintype "bidirectional"))
    )
    (net (code "46") (name "Net-(U$1-ANT)") (class "Default")
      (node (ref "C20") (pin "1") (pinfunction "1_1") (pintype "passive"))
      (node (ref "U$1") (pin "56") (pinfunction "ANT_56") (pintype "bidirectional"))
    )
    (net (code "47") (name "Net-(U$1-MIC_BIAS)") (class "Default")
      (node (ref "R16") (pin "2") (pinfunction "2_2") (pintype "passive"))
      (node (ref "U$1") (pin "46") (pinfunction "MIC_BIAS_46") (pintype "bidirectional"))
    )
    (net (code "48") (name "Net-(U$1-MIC_GND)") (class "Default")
      (node (ref "C19") (pin "1") (pinfunction "1_1") (pintype "passive"))
      (node (ref "R17") (pin "2") (pinfunction "2_2") (pintype "passive"))
      (node (ref "U$1") (pin "47") (pinfunction "MIC_GND_47") (pintype "bidirectional"))
      (node (ref "U$14") (pin "2") (pinfunction "2_2") (pintype "passive"))
    )
    (net (code "49") (name "Net-(U$1-MIC_N)") (class "Default")
      (node (ref "C18") (pin "1") (pinfunction "1_1") (pintype "passive"))
      (node (ref "U$1") (pin "48") (pinfunction "MIC_N_48") (pintype "bidirectional"))
    )
    (net (code "50") (name "Net-(U$1-MIC_P)") (class "Default")
      (node (ref "C17") (pin "1") (pinfunction "1_1") (pintype "passive"))
      (node (ref "U$1") (pin "49") (pinfunction "MIC_P_49") (pintype "bidirectional"))
    )
    (net (code "51") (name "Net-(U$1-SPK_N)") (class "Default")
      (node (ref "C14") (pin "2") (pinfunction "2_2") (pintype "passive"))
      (node (ref "C16") (pin "1") (pinfunction "1_1") (pintype "passive"))
      (node (ref "U$1") (pin "45") (pinfunction "SPK_N_45") (pintype "bidirectional"))
      (node (ref "U$14") (pin "1") (pinfunction "1_1") (pintype "passive"))
      (node (ref "U$17") (pin "2") (pinfunction "P$2_2") (pintype "bidirectional"))
      (node (ref "U$8") (pin "4") (pinfunction "P$4_4") (pintype "bidirectional"))
    )
    (net (code "52") (name "Net-(U$1-SPK_P)") (class "Default")
      (node (ref "C15") (pin "1") (pinfunction "1_1") (pintype "passive"))
      (node (ref "U$1") (pin "44") (pinfunction "SPK_P_44") (pintype "bidirectional"))
      (node (ref "U$16") (pin "1") (pinfunction "P$1_1") (pintype "bidirectional"))
      (node (ref "U$8") (pin "2") (pinfunction "P$2_2") (pintype "bidirectional"))
      (node (ref "U$8") (pin "3") (pinfunction "P$3_3") (pintype "bidirectional"))
    )
    (net (code "53") (name "Net-(U$4-PROG)") (class "Default")
      (node (ref "R6") (pin "2") (pinfunction "2_2") (pintype "passive"))
      (node (ref "U$4") (pin "5") (pinfunction "PROG_5") (pintype "bidirectional"))
    )
    (net (code "54") (name "Net-(U$4-STAT)") (class "Default")
      (node (ref "LED5") (pin "C") (pinfunction "C_C") (pintype "passive"))
      (node (ref "U$4") (pin "1") (pinfunction "STAT_1") (pintype "bidirectional"))
    )
    (net (code "55") (name "Net-(U$7-P$1)") (class "Default")
      (node (ref "C20") (pin "2") (pinfunction "2_2") (pintype "passive"))
      (node (ref "U$7") (pin "1") (pinfunction "P$1_1") (pintype "bidirectional"))
    )
    (net (code "56") (name "Net-(U$9-D)") (class "Default")
      (node (ref "R1") (pin "1") (pinfunction "1_1") (pintype "passive"))
      (node (ref "U$9") (pin "3") (pinfunction "D_3") (pintype "bidirectional"))
    )
    (net (code "57") (name "Net-(U$9-G)") (class "Default")
      (node (ref "R13") (pin "1") (pinfunction "1_1") (pintype "passive"))
      (node (ref "R2") (pin "1") (pinfunction "1_1") (pintype "passive"))
      (node (ref "U$9") (pin "1") (pinfunction "G_1") (pintype "bidirectional"))
    )
    (net (code "58") (name "Net-(U$10-D)") (class "Default")
      (node (ref "R3") (pin "1") (pinfunction "1_1") (pintype "passive"))
      (node (ref "U$10") (pin "3") (pinfunction "D_3") (pintype "bidirectional"))
    )
    (net (code "59") (name "Net-(U$10-G)") (class "Default")
      (node (ref "R12") (pin "1") (pinfunction "1_1") (pintype "passive"))
      (node (ref "R4") (pin "1") (pinfunction "1_1") (pintype "passive"))
      (node (ref "U$10") (pin "1") (pinfunction "G_1") (pintype "bidirectional"))
    )
    (net (code "60") (name "Net-(U$11-D)") (class "Default")
      (node (ref "R21") (pin "1") (pinfunction "1_1") (pintype "passive"))
      (node (ref "U$11") (pin "3") (pinfunction "D_3") (pintype "bidirectional"))
    )
    (net (code "61") (name "Net-(U$11-G)") (class "Default")
      (node (ref "R11") (pin "1") (pinfunction "1_1") (pintype "passive"))
      (node (ref "R22") (pin "1") (pinfunction "1_1") (pintype "passive"))
      (node (ref "U$11") (pin "1") (pinfunction "G_1") (pintype "bidirectional"))
    )
    (net (code "62") (name "Net-(U$12-D)") (class "Default")
      (node (ref "R23") (pin "1") (pinfunction "1_1") (pintype "passive"))
      (node (ref "U$12") (pin "3") (pinfunction "D_3") (pintype "bidirectional"))
    )
    (net (code "63") (name "Net-(U$12-G)") (class "Default")
      (node (ref "R10") (pin "1") (pinfunction "1_1") (pintype "passive"))
      (node (ref "R24") (pin "1") (pinfunction "1_1") (pintype "passive"))
      (node (ref "U$12") (pin "1") (pinfunction "G_1") (pintype "bidirectional"))
    )
    (net (code "64") (name "Net-(U$18-P$2)") (class "Default")
      (node (ref "C13") (pin "2") (pinfunction "2_2") (pintype "passive"))
      (node (ref "U$13") (pin "1") (pinfunction "1_1") (pintype "passive"))
      (node (ref "U$18") (pin "2") (pinfunction "P$2_2") (pintype "bidirectional"))
      (node (ref "U$8") (pin "1") (pinfunction "P$1_1") (pintype "bidirectional"))
    )
    (net (code "65") (name "Net-(U$19-GP0{slash}SSPND)") (class "Default")
      (node (ref "LED11") (pin "C") (pinfunction "C_C") (pintype "passive"))
      (node (ref "U$19") (pin "16") (pinfunction "GP0/SSPND_16") (pintype "bidirectional"))
    )
    (net (code "66") (name "Net-(U$19-GP1{slash}USBCFG)") (class "Default")
      (node (ref "LED12") (pin "C") (pinfunction "C_C") (pintype "passive"))
      (node (ref "U$19") (pin "15") (pinfunction "GP1/USBCFG_15") (pintype "bidirectional"))
    )
    (net (code "67") (name "Net-(U$19-GP6{slash}RXLED)") (class "Default")
      (node (ref "LED6") (pin "C") (pinfunction "C_C") (pintype "passive"))
      (node (ref "U$19") (pin "6") (pinfunction "GP6/RXLED_6") (pintype "bidirectional"))
    )
    (net (code "68") (name "Net-(U$19-GP7{slash}TXLED)") (class "Default")
      (node (ref "LED7") (pin "C") (pinfunction "C_C") (pintype "passive"))
      (node (ref "U$19") (pin "5") (pinfunction "GP7/TXLED_5") (pintype "bidirectional"))
    )
    (net (code "69") (name "Net-(U$19-OSC1)") (class "Default")
      (node (ref "U$19") (pin "2") (pinfunction "OSC1_2") (pintype "bidirectional"))
      (node (ref "U$20") (pin "3") (pinfunction "OUT_3") (pintype "bidirectional"))
    )
    (net (code "70") (name "Net-(U$19-OSC2)") (class "Default")
      (node (ref "U$19") (pin "3") (pinfunction "OSC2_3") (pintype "bidirectional"))
      (node (ref "U$20") (pin "1") (pinfunction "IN_1") (pintype "bidirectional"))
    )
    (net (code "71") (name "Net-(U1-PA0)") (class "Default")
      (node (ref "R20") (pin "1") (pinfunction "1_1") (pintype "passive"))
      (node (ref "U1") (pin "9") (pinfunction "PA0_9") (pintype "bidirectional"))
    )
    (net (code "72") (name "Net-(U1-PA1)") (class "Default")
      (node (ref "R19") (pin "1") (pinfunction "1_1") (pintype "passive"))
      (node (ref "U1") (pin "8") (pinfunction "PA1_8") (pintype "bidirectional"))
    )
    (net (code "73") (name "Net-(U2-DIR1)") (class "Default")
      (node (ref "R8") (pin "2") (pinfunction "2_2") (pintype "passive"))
      (node (ref "U2") (pin "1") (pinfunction "DIR1_1") (pintype "input"))
    )
    (net (code "74") (name "Net-(U2-DIR2)") (class "Default")
      (node (ref "R9") (pin "1") (pinfunction "1_1") (pintype "passive"))
      (node (ref "U2") (pin "2") (pinfunction "DIR2_2") (pintype "input"))
    )
    (net (code "75") (name "Net-(U2-DIR3)") (class "Default")
      (node (ref "R39") (pin "2") (pinfunction "2_2") (pintype "passive"))
      (node (ref "U2") (pin "7") (pinfunction "DIR3_7") (pintype "input"))
    )
    (net (code "76") (name "Net-(U2-DIR4)") (class "Default")
      (node (ref "R40") (pin "2") (pinfunction "2_2") (pintype "passive"))
      (node (ref "U2") (pin "8") (pinfunction "DIR4_8") (pintype "input"))
    )
    (net (code "77") (name "Net-(U2-~{OE})") (class "Default")
      (node (ref "R41") (pin "2") (pinfunction "2_2") (pintype "passive"))
      (node (ref "U2") (pin "9") (pinfunction "~{OE}_9") (pintype "input"))
    )
    (net (code "78") (name "POWER_IN") (class "Default")
      (node (ref "C1") (pin "1") (pinfunction "1_1") (pintype "passive"))
      (node (ref "C21") (pin "2") (pinfunction "2_2") (pintype "passive"))
      (node (ref "C22") (pin "2") (pinfunction "2_2") (pintype "passive"))
      (node (ref "C23") (pin "2") (pinfunction "2_2") (pintype "passive"))
      (node (ref "C24") (pin "2") (pinfunction "2_2") (pintype "passive"))
      (node (ref "C25") (pin "2") (pinfunction "2_2") (pintype "passive"))
      (node (ref "C28") (pin "1") (pinfunction "1_1") (pintype "passive"))
      (node (ref "LED1") (pin "A") (pinfunction "A_A") (pintype "passive"))
      (node (ref "LED2") (pin "A") (pinfunction "A_A") (pintype "passive"))
      (node (ref "LED3") (pin "A") (pinfunction "A_A") (pintype "passive"))
      (node (ref "LED4") (pin "A") (pinfunction "A_A") (pintype "passive"))
      (node (ref "U$1") (pin "51") (pinfunction "VCC_51") (pintype "bidirectional"))
      (node (ref "U$1") (pin "52") (pinfunction "VCC_52") (pintype "bidirectional"))
      (node (ref "U$1") (pin "53") (pinfunction "VCC_53") (pintype "bidirectional"))
      (node (ref "U$23") (pin "1") (pinfunction "IN_1") (pintype "bidirectional"))
      (node (ref "U$23") (pin "3") (pinfunction "EN_3") (pintype "bidirectional"))
      (node (ref "U$3") (pin "1") (pinfunction "IN_1") (pintype "bidirectional"))
      (node (ref "U$3") (pin "3") (pinfunction "EN_3") (pintype "bidirectional"))
      (node (ref "U$6") (pin "3") (pinfunction "3_3") (pintype "bidirectional"))
    )
    (net (code "79") (name "POWER_ON") (class "Default")
      (node (ref "R18") (pin "1") (pinfunction "1_1") (pintype "passive"))
      (node (ref "R19") (pin "2") (pinfunction "2_2") (pintype "passive"))
      (node (ref "S6") (pin "3") (pinfunction "P_3") (pintype "passive"))
      (node (ref "S6") (pin "4") (pinfunction "P1_4") (pintype "passive"))
      (node (ref "U$1") (pin "15") (pinfunction "PWR_ON_15") (pintype "bidirectional"))
    )
    (net (code "80") (name "RESETN") (class "Default")
      (node (ref "JP1") (pin "3") (pinfunction "3_3") (pintype "passive"))
      (node (ref "S3") (pin "3") (pinfunction "P_3") (pintype "passive"))
      (node (ref "S3") (pin "4") (pinfunction "P1_4") (pintype "passive"))
      (node (ref "U1") (pin "14") (pinfunction "PC3_14") (pintype "bidirectional"))
    )
    (net (code "81") (name "RESET_N") (class "Default")
      (node (ref "R20") (pin "2") (pinfunction "2_2") (pintype "passive"))
      (node (ref "S1") (pin "1") (pinfunction "S_1") (pintype "passive"))
      (node (ref "U$1") (pin "18") (pinfunction "RESET_N_18") (pintype "bidirectional"))
    )
    (net (code "82") (name "RX_33") (class "Default")
      (node (ref "JP2") (pin "2") (pinfunction "2_2") (pintype "passive"))
      (node (ref "U1") (pin "2") (pinfunction "PA7_2") (pintype "bidirectional"))
      (node (ref "U2") (pin "5") (pinfunction "A3_5") (pintype "bidirectional"))
    )
    (net (code "83") (name "SCK") (class "Default")
      (node (ref "JP1") (pin "6") (pinfunction "6_6") (pintype "passive"))
      (node (ref "U1") (pin "16") (pinfunction "PC1_16") (pintype "bidirectional"))
    )
    (net (code "84") (name "TX_33") (class "Default")
      (node (ref "JP2") (pin "3") (pinfunction "3_3") (pintype "passive"))
      (node (ref "U1") (pin "1") (pinfunction "PB0_1") (pintype "bidirectional"))
      (node (ref "U2") (pin "6") (pinfunction "A4_6") (pintype "bidirectional"))
    )
    (net (code "85") (name "USB_CTS") (class "Default")
      (node (ref "U$19") (pin "13") (pinfunction "CTS_13") (pintype "bidirectional"))
      (node (ref "U1") (pin "5") (pinfunction "PA4_5") (pintype "bidirectional"))
    )
    (net (code "86") (name "USB_RTS") (class "Default")
      (node (ref "U$19") (pin "11") (pinfunction "RTS_11") (pintype "bidirectional"))
      (node (ref "U1") (pin "4") (pinfunction "PA5_4") (pintype "bidirectional"))
    )
    (net (code "87") (name "VUSB") (class "Default")
      (node (ref "C34") (pin "1") (pinfunction "1_1") (pintype "passive"))
      (node (ref "C4") (pin "1") (pinfunction "1_1") (pintype "passive"))
      (node (ref "C6") (pin "1") (pinfunction "1_1") (pintype "passive"))
      (node (ref "R29") (pin "1") (pinfunction "1_1") (pintype "passive"))
      (node (ref "R30") (pin "1") (pinfunction "1_1") (pintype "passive"))
      (node (ref "R31") (pin "2") (pinfunction "2_2") (pintype "passive"))
      (node (ref "R32") (pin "2") (pinfunction "2_2") (pintype "passive"))
      (node (ref "R5") (pin "2") (pinfunction "2_2") (pintype "passive"))
      (node (ref "R7") (pin "1") (pinfunction "1_1") (pintype "passive"))
      (node (ref "U$19") (pin "1") (pinfunction "VDD_1") (pintype "bidirectional"))
      (node (ref "U$19") (pin "17") (pinfunction "VUSB_17") (pintype "bidirectional"))
      (node (ref "U$4") (pin "4") (pinfunction "VIN_4") (pintype "bidirectional"))
      (node (ref "U$5") (pin "P$1") (pinfunction "VCC_P$1") (pintype "bidirectional"))
    )
    (net (code "88") (name "unconnected-(S1-P1-Pad4)") (class "Default")
      (node (ref "S1") (pin "4") (pinfunction "P1_4") (pintype "passive"))
    )
    (net (code "89") (name "unconnected-(S1-S1-Pad2)") (class "Default")
      (node (ref "S1") (pin "2") (pinfunction "S1_2") (pintype "passive"))
    )
    (net (code "90") (name "unconnected-(S2-P1-Pad4)") (class "Default")
      (node (ref "S2") (pin "4") (pinfunction "P1_4") (pintype "passive"))
    )
    (net (code "91") (name "unconnected-(S2-S1-Pad2)") (class "Default")
      (node (ref "S2") (pin "2") (pinfunction "S1_2") (pintype "passive"))
    )
    (net (code "92") (name "unconnected-(S6-S-Pad1)") (class "Default")
      (node (ref "S6") (pin "1") (pinfunction "S_1") (pintype "passive"))
    )
    (net (code "93") (name "unconnected-(U$1-ANT_DET-Pad62)") (class "Default")
      (node (ref "U$1") (pin "62") (pinfunction "ANT_DET_62") (pintype "bidirectional"))
    )
    (net (code "94") (name "unconnected-(U$1-DCD-Pad8)") (class "Default")
      (node (ref "U$1") (pin "8") (pinfunction "DCD_8") (pintype "bidirectional"))
    )
    (net (code "95") (name "unconnected-(U$1-DSR-Pad6)") (class "Default")
      (node (ref "U$1") (pin "6") (pinfunction "DSR_6") (pintype "bidirectional"))
    )
    (net (code "96") (name "unconnected-(U$1-I2S_CLK-Pad36)") (class "Default")
      (node (ref "U$1") (pin "36") (pinfunction "I2S_CLK_36") (pintype "bidirectional"))
    )
    (net (code "97") (name "unconnected-(U$1-I2S_RXD-Pad37)") (class "Default")
      (node (ref "U$1") (pin "37") (pinfunction "I2S_RXD_37") (pintype "bidirectional"))
    )
    (net (code "98") (name "unconnected-(U$1-I2S_TXD-Pad35)") (class "Default")
      (node (ref "U$1") (pin "35") (pinfunction "I2S_TXD_35") (pintype "bidirectional"))
    )
    (net (code "99") (name "unconnected-(U$1-I2S_WA-Pad34)") (class "Default")
      (node (ref "U$1") (pin "34") (pinfunction "I2S_WA_34") (pintype "bidirectional"))
    )
    (net (code "100") (name "unconnected-(U$1-RI-Pad7)") (class "Default")
      (node (ref "U$1") (pin "7") (pinfunction "RI_7") (pintype "bidirectional"))
    )
    (net (code "101") (name "unconnected-(U$1-RXD_AUX-Pad28)") (class "Default")
      (node (ref "U$1") (pin "28") (pinfunction "RXD_AUX_28") (pintype "bidirectional"))
    )
    (net (code "102") (name "unconnected-(U$1-SCL-Pad27)") (class "Default")
      (node (ref "U$1") (pin "27") (pinfunction "SCL_27") (pintype "bidirectional"))
    )
    (net (code "103") (name "unconnected-(U$1-SDA-Pad26)") (class "Default")
      (node (ref "U$1") (pin "26") (pinfunction "SDA_26") (pintype "bidirectional"))
    )
    (net (code "104") (name "unconnected-(U$1-SIM_DET-Pad42)") (class "Default")
      (node (ref "U$1") (pin "42") (pinfunction "SIM_DET_42") (pintype "bidirectional"))
    )
    (net (code "105") (name "unconnected-(U$1-TXD_AUX-Pad29)") (class "Default")
      (node (ref "U$1") (pin "29") (pinfunction "TXD_AUX_29") (pintype "bidirectional"))
    )
    (net (code "106") (name "unconnected-(U$1-V_INT-Pad4)") (class "Default")
      (node (ref "U$1") (pin "4") (pinfunction "V_INT_4") (pintype "bidirectional"))
    )
    (net (code "107") (name "unconnected-(U$2-CD{slash}DAT3-PadT2)") (class "Default")
      (node (ref "U$2") (pin "T2") (pinfunction "CD/DAT3_T2") (pintype "bidirectional"))
    )
    (net (code "108") (name "unconnected-(U$2-CMD-PadT3)") (class "Default")
      (node (ref "U$2") (pin "T3") (pinfunction "CMD_T3") (pintype "bidirectional"))
    )
    (net (code "109") (name "unconnected-(U$2-DAT0-PadT7)") (class "Default")
      (node (ref "U$2") (pin "T7") (pinfunction "DAT0_T7") (pintype "bidirectional"))
    )
    (net (code "110") (name "unconnected-(U$2-DAT1-PadT8)") (class "Default")
      (node (ref "U$2") (pin "T8") (pinfunction "DAT1_T8") (pintype "bidirectional"))
    )
    (net (code "111") (name "unconnected-(U$2-DAT2-PadT1)") (class "Default")
      (node (ref "U$2") (pin "T1") (pinfunction "DAT2_T1") (pintype "bidirectional"))
    )
    (net (code "112") (name "unconnected-(U$2-SDCLK-PadT5)") (class "Default")
      (node (ref "U$2") (pin "T5") (pinfunction "SDCLK_T5") (pintype "bidirectional"))
    )
    (net (code "113") (name "unconnected-(U$2-SD_DET-PadSW)") (class "Default")
      (node (ref "U$2") (pin "SW") (pinfunction "SD_DET_SW") (pintype "bidirectional"))
    )
    (net (code "114") (name "unconnected-(U$2-VDD-PadT4)") (class "Default")
      (node (ref "U$2") (pin "T4") (pinfunction "VDD_T4") (pintype "bidirectional"))
    )
    (net (code "115") (name "unconnected-(U$2-VPP-PadC6)") (class "Default")
      (node (ref "U$2") (pin "C6") (pinfunction "VPP_C6") (pintype "bidirectional"))
    )
    (net (code "116") (name "unconnected-(U$5-ID-PadP$4)") (class "Default")
      (node (ref "U$5") (pin "P$4") (pinfunction "ID_P$4") (pintype "bidirectional"))
    )
    (net (code "117") (name "unconnected-(U$19-GP2-Pad14)") (class "Default")
      (node (ref "U$19") (pin "14") (pinfunction "GP2_14") (pintype "bidirectional"))
    )
    (net (code "118") (name "unconnected-(U$19-GP3-Pad9)") (class "Default")
      (node (ref "U$19") (pin "9") (pinfunction "GP3_9") (pintype "bidirectional"))
    )
    (net (code "119") (name "unconnected-(U$19-GP4-Pad8)") (class "Default")
      (node (ref "U$19") (pin "8") (pinfunction "GP4_8") (pintype "bidirectional"))
    )
    (net (code "120") (name "unconnected-(U$19-GP5-Pad7)") (class "Default")
      (node (ref "U$19") (pin "7") (pinfunction "GP5_7") (pintype "bidirectional"))
    )
    (net (code "121") (name "unconnected-(U1-PA6-Pad3)") (class "Default")
      (node (ref "U1") (pin "3") (pinfunction "PA6_3") (pintype "bidirectional"))
    )
    (net (code "122") (name "unconnected-(U1-PC2-Pad15)") (class "Default")
      (node (ref "U1") (pin "15") (pinfunction "PC2_15") (pintype "bidirectional"))
    )
    (net (code "123") (name "unconnected-(U1-PC4-Pad13)") (class "Default")
      (node (ref "U1") (pin "13") (pinfunction "PC4_13") (pintype "bidirectional"))
    )
    (net (code "124") (name "unconnected-(U1-PC5-Pad12)") (class "Default")
      (node (ref "U1") (pin "12") (pinfunction "PC5_12") (pintype "bidirectional"))
    )
  )
)
